# ProPrj_OASman_SMD_update_2025-02-10.net
KiCad netlist of a schematic drawn in EasyEDA Pro
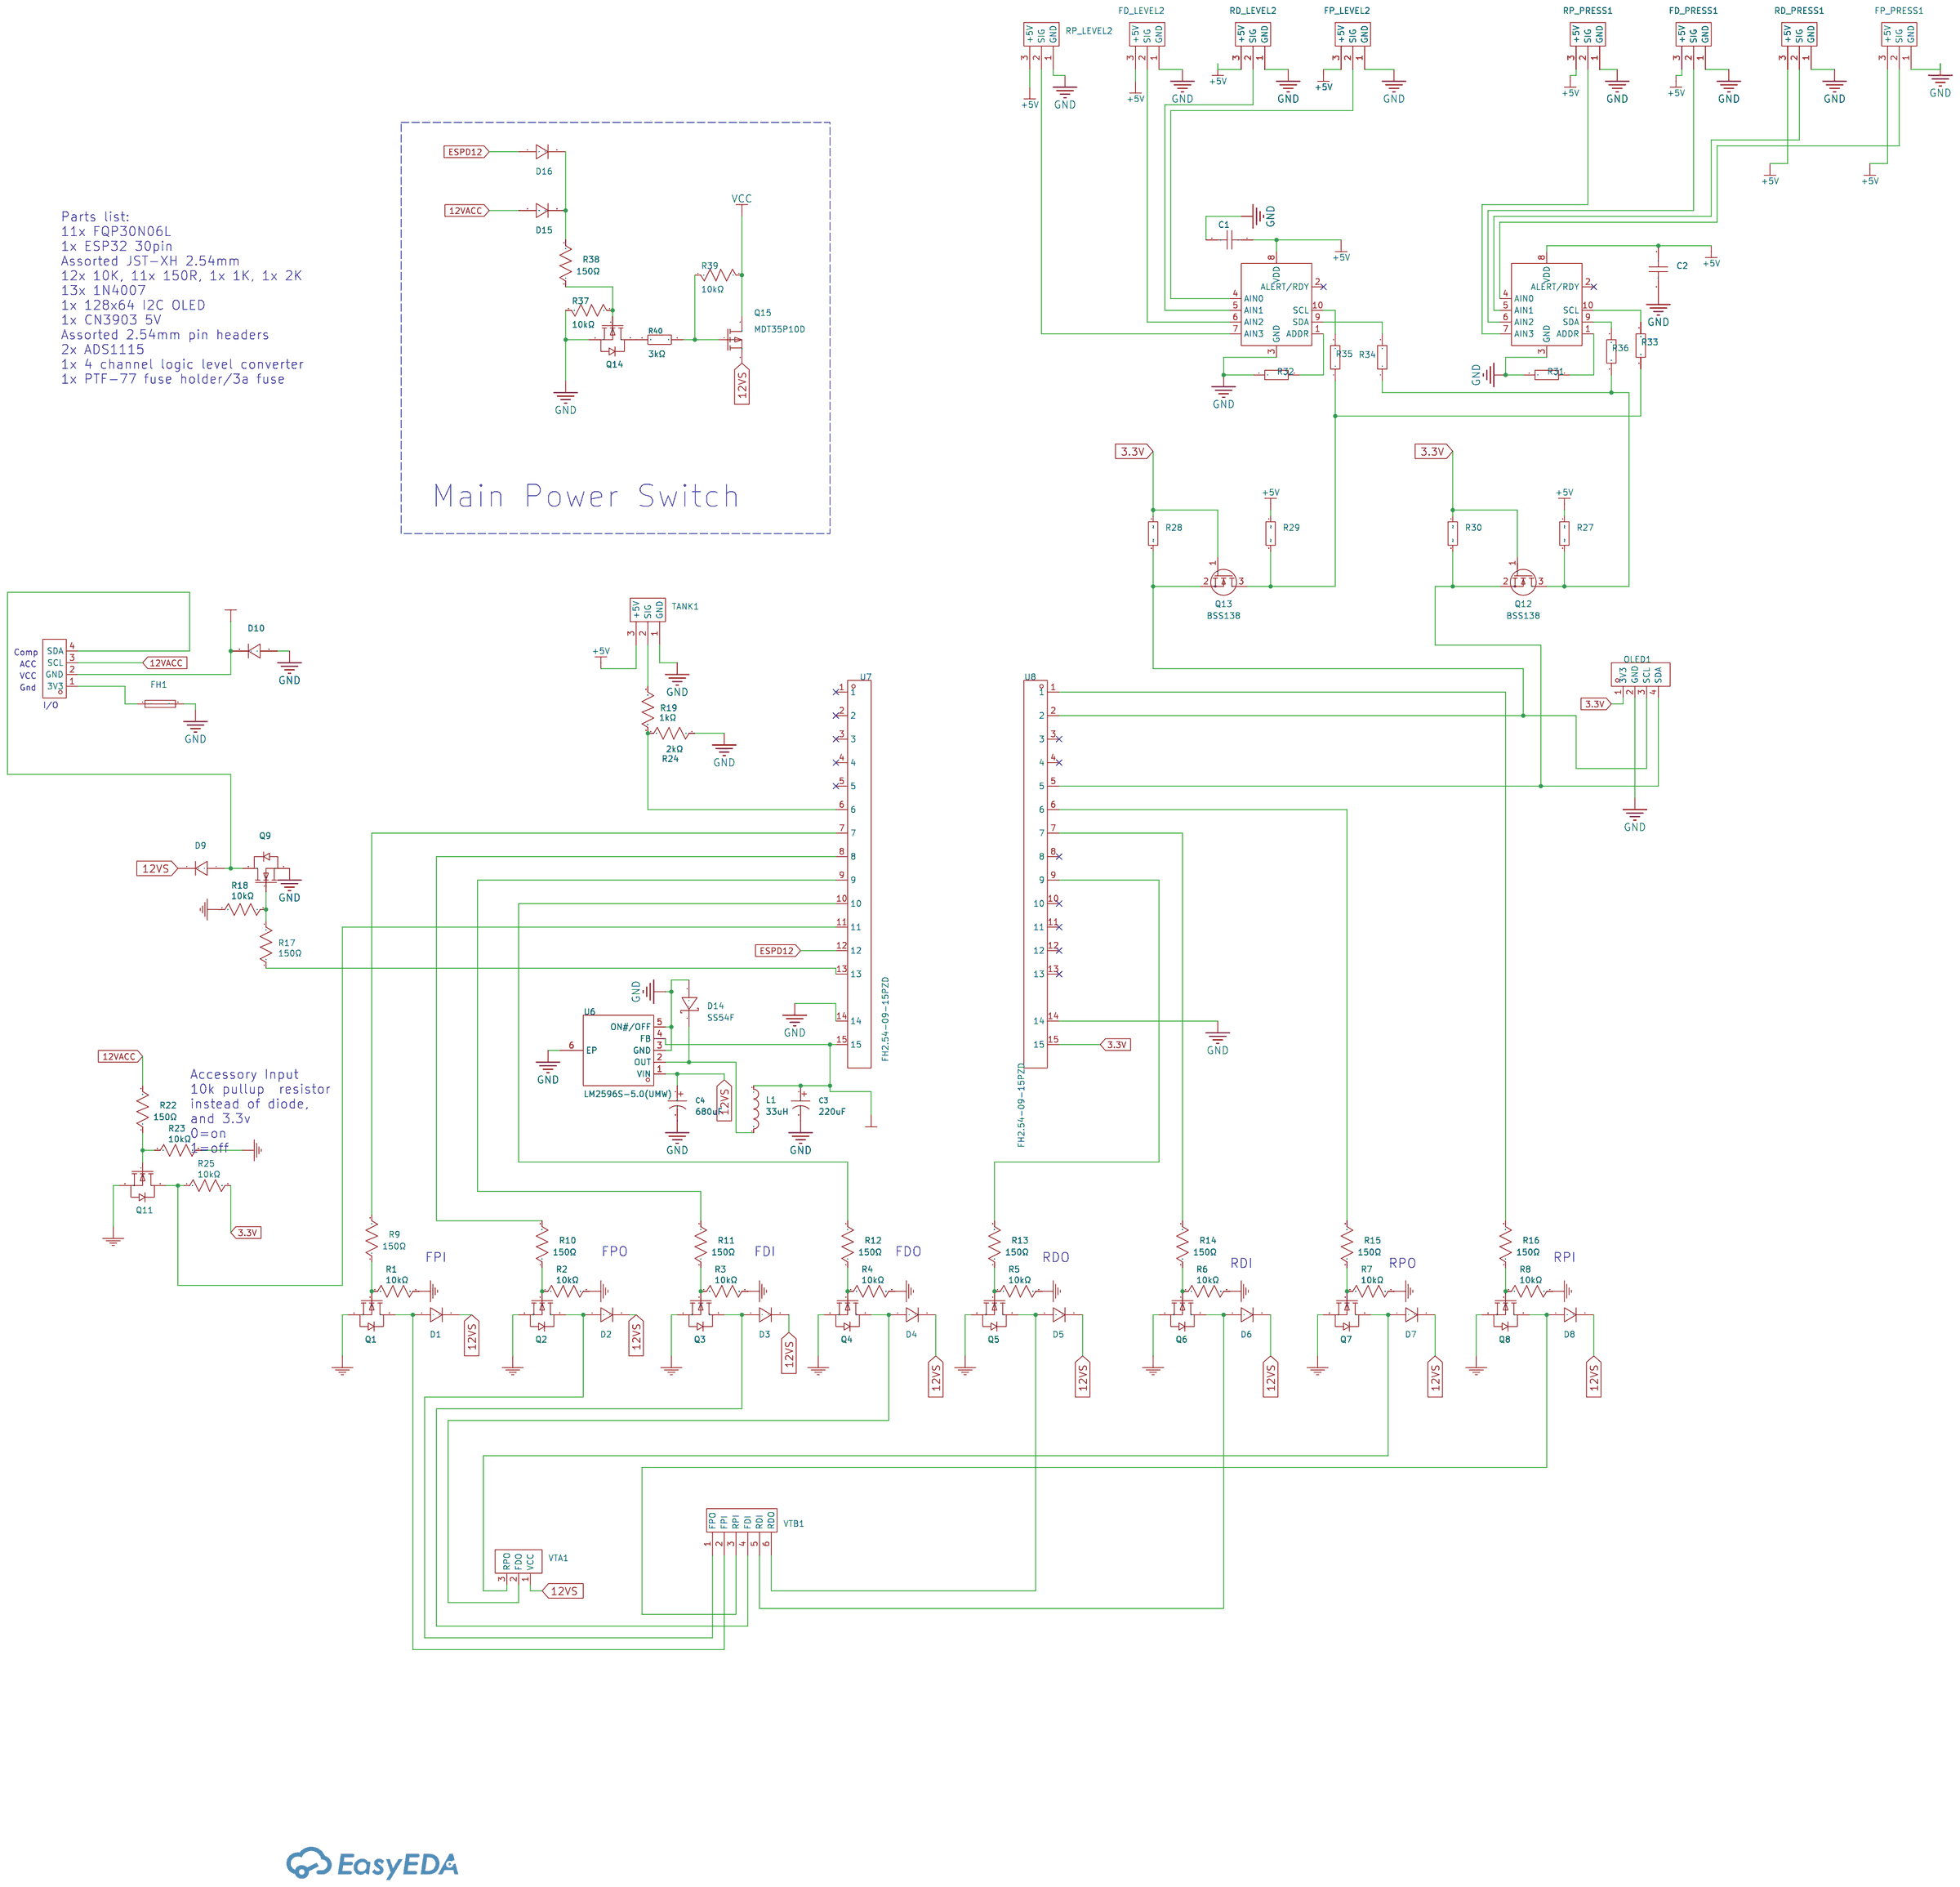
[diagram p0: schematic sheet]

(export (version "E")
  (design (tool "Eeschema 10.0.6"))
  (components
    (comp (ref "C1")
      (value "1uF")
      (footprint "easyedapro:C0603")
      (fields
        (field (name "Manufacturer Part") "GRM188R61H105KAALD")
        (field (name "Manufacturer") "muRata(村田)")
      )
      (libsource (lib "easyedapro") (part "GRM188R61H105KAALD"))
    )
    (comp (ref "C2")
      (value "1uF")
      (footprint "easyedapro:C0603")
      (fields
        (field (name "Manufacturer Part") "GRM188R61H105KAALD")
        (field (name "Manufacturer") "muRata(村田)")
      )
      (libsource (lib "easyedapro") (part "GRM188R61H105KAALD"))
    )
    (comp (ref "C3")
      (value "220uF")
      (footprint "easyedapro:CAP-SMD_BD6.3-L6.6-W6.6-FD")
      (fields (field (name "Manufacturer Part") "CK1C221M-CRE77") (field (name "Manufacturer") "ST(先科)"))
      (libsource (lib "easyedapro") (part "CK1C221M-CRE77"))
    )
    (comp (ref "C4")
      (value "680uF")
      (footprint "easyedapro:CAP-SMD_BD10.0-L10.3-W10.3-LS11.3-FD")
      (fields (field (name "Manufacturer Part") "VT1E681M1013") (field (name "Manufacturer") "HONOR(荣誉)"))
      (libsource (lib "easyedapro") (part "CVT1E681M1013"))
    )
    (comp (ref "CN1")
      (value "XH-4A绿色")
      (footprint "easyedapro:CONN-TH_XH-4A-1")
      (fields (field (name "Manufacturer") "BOOMELE(博穆精密)"))
      (libsource (lib "easyedapro") (part "XH-4A绿色"))
    )
    (comp (ref "D1") (value "1N4007") (libsource (lib "easyedapro") (part "1N4007")))
    (comp (ref "D2") (value "1N4007") (libsource (lib "easyedapro") (part "1N4007")))
    (comp (ref "D3") (value "1N4007") (libsource (lib "easyedapro") (part "1N4007")))
    (comp (ref "D4") (value "1N4007") (libsource (lib "easyedapro") (part "1N4007")))
    (comp (ref "D5") (value "1N4007") (libsource (lib "easyedapro") (part "1N4007")))
    (comp (ref "D6") (value "1N4007") (libsource (lib "easyedapro") (part "1N4007")))
    (comp (ref "D7") (value "1N4007") (libsource (lib "easyedapro") (part "1N4007")))
    (comp (ref "D8") (value "1N4007") (libsource (lib "easyedapro") (part "1N4007")))
    (comp (ref "D9") (value "1N4007") (libsource (lib "easyedapro") (part "1N4007")))
    (comp (ref "D10") (value "1N4007") (libsource (lib "easyedapro") (part "1N4007")))
    (comp (ref "D14")
      (value "SS54F")
      (footprint "easyedapro:SMAF_L3.5-W2.6-LS4.7-FD")
      (fields (field (name "Manufacturer") "High Diode(海德)"))
      (libsource (lib "easyedapro") (part "SS54F_C524830"))
    )
    (comp (ref "D15") (value "1N4007") (libsource (lib "easyedapro") (part "1N4007")))
    (comp (ref "D16") (value "1N4007") (libsource (lib "easyedapro") (part "1N4007")))
    (comp (ref "FD_LEVEL2")
      (value "XH-3A")
      (footprint "easyedapro:CONN-TH_XH-3A")
      (fields (field (name "Manufacturer") "BOOMELE(博穆精密)"))
      (libsource (lib "easyedapro") (part "XH-3A"))
    )
    (comp (ref "FD_PRESS1")
      (value "XH-3A")
      (footprint "easyedapro:CONN-TH_XH-3A")
      (fields (field (name "Manufacturer") "BOOMELE(博穆精密)"))
      (libsource (lib "easyedapro") (part "XH-3A"))
    )
    (comp (ref "FH1")
      (value "PTF-77")
      (description "Fuseholder Type:- Voltage Rating:250V Current Rating:10A Fuse Type:- Fuse Size:-")
      (libsource (lib "easyedapro") (part "PTF-77"))
    )
    (comp (ref "FP_LEVEL2")
      (value "XH-3A")
      (footprint "easyedapro:CONN-TH_XH-3A")
      (fields (field (name "Manufacturer") "BOOMELE(博穆精密)"))
      (libsource (lib "easyedapro") (part "XH-3A"))
    )
    (comp (ref "FP_PRESS1")
      (value "XH-3A")
      (footprint "easyedapro:CONN-TH_XH-3A")
      (fields (field (name "Manufacturer") "BOOMELE(博穆精密)"))
      (libsource (lib "easyedapro") (part "XH-3A"))
    )
    (comp (ref "L1")
      (value "33uH")
      (footprint "easyedapro:IND-SMD_L10.8-W10.0_SLO1040H")
      (fields
        (field (name "Manufacturer Part") "SLO1040H330MTT")
        (field (name "Manufacturer") "Sunltech(韩国顺磁)")
      )
      (libsource (lib "easyedapro") (part "SLO1040H330MTT"))
    )
    (comp (ref "OLED1")
      (value "XH-4A绿色")
      (footprint "easyedapro:CONN-TH_XH-4A-1")
      (fields (field (name "Manufacturer") "BOOMELE(博穆精密)"))
      (libsource (lib "easyedapro") (part "XH-4A绿色"))
    )
    (comp (ref "Q1") (value "MDT30N06L") (libsource (lib "easyedapro") (part "FQP30N06L")))
    (comp (ref "Q2") (value "MDT30N06L") (libsource (lib "easyedapro") (part "FQP30N06L")))
    (comp (ref "Q3") (value "MDT30N06L") (libsource (lib "easyedapro") (part "FQP30N06L")))
    (comp (ref "Q4") (value "MDT30N06L") (libsource (lib "easyedapro") (part "FQP30N06L")))
    (comp (ref "Q5") (value "MDT30N06L") (libsource (lib "easyedapro") (part "FQP30N06L")))
    (comp (ref "Q6") (value "MDT30N06L") (libsource (lib "easyedapro") (part "FQP30N06L")))
    (comp (ref "Q7") (value "MDT30N06L") (libsource (lib "easyedapro") (part "FQP30N06L")))
    (comp (ref "Q8") (value "MDT30N06L") (libsource (lib "easyedapro") (part "FQP30N06L")))
    (comp (ref "Q9") (value "MDT30N06L") (libsource (lib "easyedapro") (part "FQP30N06L")))
    (comp (ref "Q11") (value "MDT30N06L") (libsource (lib "easyedapro") (part "FQP30N06L")))
    (comp (ref "Q12")
      (value "BSS138")
      (footprint "easyedapro:PCM_Package_TO_SOT_SMD_AKL:SOT-23")
      (description "SOT-23 N-MOSFET enchancement mode transistor, 50V, 200mA, 300mW, Alternate KiCAD Library")
      (libsource (lib "easyedapro") (part "PCM_Transistor_MOSFET_AKL_BSS138"))
    )
    (comp (ref "Q13")
      (value "BSS138")
      (footprint "easyedapro:PCM_Package_TO_SOT_SMD_AKL:SOT-23")
      (description "SOT-23 N-MOSFET enchancement mode transistor, 50V, 200mA, 300mW, Alternate KiCAD Library")
      (libsource (lib "easyedapro") (part "PCM_Transistor_MOSFET_AKL_BSS138"))
    )
    (comp (ref "Q14") (value "MDT30N06L") (libsource (lib "easyedapro") (part "FQP30N06L")))
    (comp (ref "Q15")
      (value "MDT35P10D")
      (footprint "easyedapro:TO-252-2_L6.6-W6.1-P4.57-LS9.9-BR-CW")
      (fields (field (name "Manufacturer") "minos(迈诺斯)"))
      (libsource (lib "easyedapro") (part "MDT35P10D"))
    )
    (comp (ref "R1")
      (value "10kΩ")
      (fields (field (name "Manufacturer") "UNI-ROYAL(厚声)"))
      (libsource (lib "easyedapro") (part "10k"))
    )
    (comp (ref "R2")
      (value "10kΩ")
      (fields (field (name "Manufacturer") "UNI-ROYAL(厚声)"))
      (libsource (lib "easyedapro") (part "10k"))
    )
    (comp (ref "R3")
      (value "10kΩ")
      (fields (field (name "Manufacturer") "UNI-ROYAL(厚声)"))
      (libsource (lib "easyedapro") (part "10k"))
    )
    (comp (ref "R4")
      (value "10kΩ")
      (fields (field (name "Manufacturer") "UNI-ROYAL(厚声)"))
      (libsource (lib "easyedapro") (part "10k"))
    )
    (comp (ref "R5")
      (value "10kΩ")
      (fields (field (name "Manufacturer") "UNI-ROYAL(厚声)"))
      (libsource (lib "easyedapro") (part "10k"))
    )
    (comp (ref "R6")
      (value "10kΩ")
      (fields (field (name "Manufacturer") "UNI-ROYAL(厚声)"))
      (libsource (lib "easyedapro") (part "10k"))
    )
    (comp (ref "R7")
      (value "10kΩ")
      (fields (field (name "Manufacturer") "UNI-ROYAL(厚声)"))
      (libsource (lib "easyedapro") (part "10k"))
    )
    (comp (ref "R8")
      (value "10kΩ")
      (fields (field (name "Manufacturer") "UNI-ROYAL(厚声)"))
      (libsource (lib "easyedapro") (part "10k"))
    )
    (comp (ref "R9")
      (value "150Ω")
      (fields (field (name "Manufacturer") "UNI-ROYAL(厚声)"))
      (libsource (lib "easyedapro") (part "150R"))
    )
    (comp (ref "R10")
      (value "150Ω")
      (fields (field (name "Manufacturer") "UNI-ROYAL(厚声)"))
      (libsource (lib "easyedapro") (part "150R"))
    )
    (comp (ref "R11")
      (value "150Ω")
      (fields (field (name "Manufacturer") "UNI-ROYAL(厚声)"))
      (libsource (lib "easyedapro") (part "150R"))
    )
    (comp (ref "R12")
      (value "150Ω")
      (fields (field (name "Manufacturer") "UNI-ROYAL(厚声)"))
      (libsource (lib "easyedapro") (part "150R"))
    )
    (comp (ref "R13")
      (value "150Ω")
      (fields (field (name "Manufacturer") "UNI-ROYAL(厚声)"))
      (libsource (lib "easyedapro") (part "150R"))
    )
    (comp (ref "R14")
      (value "150Ω")
      (fields (field (name "Manufacturer") "UNI-ROYAL(厚声)"))
      (libsource (lib "easyedapro") (part "150R"))
    )
    (comp (ref "R15")
      (value "150Ω")
      (fields (field (name "Manufacturer") "UNI-ROYAL(厚声)"))
      (libsource (lib "easyedapro") (part "150R"))
    )
    (comp (ref "R16")
      (value "150Ω")
      (fields (field (name "Manufacturer") "UNI-ROYAL(厚声)"))
      (libsource (lib "easyedapro") (part "150R"))
    )
    (comp (ref "R17")
      (value "150Ω")
      (fields (field (name "Manufacturer") "UNI-ROYAL(厚声)"))
      (libsource (lib "easyedapro") (part "150R"))
    )
    (comp (ref "R18")
      (value "10kΩ")
      (fields (field (name "Manufacturer") "UNI-ROYAL(厚声)"))
      (libsource (lib "easyedapro") (part "10k"))
    )
    (comp (ref "R19")
      (value "1kΩ")
      (fields (field (name "Manufacturer") "UNI-ROYAL(厚声)"))
      (libsource (lib "easyedapro") (part "1K"))
    )
    (comp (ref "R22")
      (value "150Ω")
      (fields (field (name "Manufacturer") "UNI-ROYAL(厚声)"))
      (libsource (lib "easyedapro") (part "150R"))
    )
    (comp (ref "R23")
      (value "10kΩ")
      (fields (field (name "Manufacturer") "UNI-ROYAL(厚声)"))
      (libsource (lib "easyedapro") (part "10k"))
    )
    (comp (ref "R24")
      (value "2kΩ")
      (fields (field (name "Manufacturer") "UNI-ROYAL(厚声)"))
      (libsource (lib "easyedapro") (part "2K"))
    )
    (comp (ref "R25")
      (value "10kΩ")
      (fields (field (name "Manufacturer") "UNI-ROYAL(厚声)"))
      (libsource (lib "easyedapro") (part "10k"))
    )
    (comp (ref "R27")
      (value "10k_0402")
      (footprint "easyedapro:Resistor_SMD:R_0402_1005Metric")
      (description "10k, 1%, 1/16W, 0603")
      (fields (field (name "Manufacturer") "Yageo"))
      (libsource (lib "easyedapro") (part "PCM_4ms_Resistor_10k_0402"))
    )
    (comp (ref "R28")
      (value "10k_0402")
      (footprint "easyedapro:Resistor_SMD:R_0402_1005Metric")
      (description "10k, 1%, 1/16W, 0603")
      (fields (field (name "Manufacturer") "Yageo"))
      (libsource (lib "easyedapro") (part "PCM_4ms_Resistor_10k_0402"))
    )
    (comp (ref "R29")
      (value "10k_0402")
      (footprint "easyedapro:Resistor_SMD:R_0402_1005Metric")
      (description "10k, 1%, 1/16W, 0603")
      (fields (field (name "Manufacturer") "Yageo"))
      (libsource (lib "easyedapro") (part "PCM_4ms_Resistor_10k_0402"))
    )
    (comp (ref "R30")
      (value "10k_0402")
      (footprint "easyedapro:Resistor_SMD:R_0402_1005Metric")
      (description "10k, 1%, 1/16W, 0603")
      (fields (field (name "Manufacturer") "Yageo"))
      (libsource (lib "easyedapro") (part "PCM_4ms_Resistor_10k_0402"))
    )
    (comp (ref "R31")
      (value "10K")
      (footprint "easyedapro:R0402")
      (libsource (lib "easyedapro") (part "Res"))
    )
    (comp (ref "R32")
      (value "10K")
      (footprint "easyedapro:R0402")
      (libsource (lib "easyedapro") (part "Res"))
    )
    (comp (ref "R33")
      (value "10K")
      (footprint "easyedapro:R0402")
      (libsource (lib "easyedapro") (part "Res"))
    )
    (comp (ref "R34")
      (value "10K")
      (footprint "easyedapro:R0402")
      (libsource (lib "easyedapro") (part "Res"))
    )
    (comp (ref "R35")
      (value "10K")
      (footprint "easyedapro:R0402")
      (libsource (lib "easyedapro") (part "Res"))
    )
    (comp (ref "R36")
      (value "10K")
      (footprint "easyedapro:R0402")
      (libsource (lib "easyedapro") (part "Res"))
    )
    (comp (ref "R37")
      (value "10kΩ")
      (fields (field (name "Manufacturer") "UNI-ROYAL(厚声)"))
      (libsource (lib "easyedapro") (part "10k"))
    )
    (comp (ref "R38")
      (value "150Ω")
      (fields (field (name "Manufacturer") "UNI-ROYAL(厚声)"))
      (libsource (lib "easyedapro") (part "150R"))
    )
    (comp (ref "R39")
      (value "10kΩ")
      (fields (field (name "Manufacturer") "UNI-ROYAL(厚声)"))
      (libsource (lib "easyedapro") (part "10k"))
    )
    (comp (ref "R40")
      (value "3kΩ")
      (footprint "easyedapro:R1206")
      (fields
        (field (name "Manufacturer Part") "1206W4F3001T5E")
        (field (name "Manufacturer") "UNI-ROYAL(厚声)")
      )
      (libsource (lib "easyedapro") (part "1206W4F3001T5E"))
    )
    (comp (ref "RD_LEVEL2")
      (value "XH-3A")
      (footprint "easyedapro:CONN-TH_XH-3A")
      (fields (field (name "Manufacturer") "BOOMELE(博穆精密)"))
      (libsource (lib "easyedapro") (part "XH-3A"))
    )
    (comp (ref "RD_PRESS1")
      (value "XH-3A")
      (footprint "easyedapro:CONN-TH_XH-3A")
      (fields (field (name "Manufacturer") "BOOMELE(博穆精密)"))
      (libsource (lib "easyedapro") (part "XH-3A"))
    )
    (comp (ref "RP_LEVEL2")
      (value "XH-3A")
      (footprint "easyedapro:CONN-TH_XH-3A")
      (fields (field (name "Manufacturer") "BOOMELE(博穆精密)"))
      (libsource (lib "easyedapro") (part "XH-3A"))
    )
    (comp (ref "RP_PRESS1")
      (value "XH-3A")
      (footprint "easyedapro:CONN-TH_XH-3A")
      (fields (field (name "Manufacturer") "BOOMELE(博穆精密)"))
      (libsource (lib "easyedapro") (part "XH-3A"))
    )
    (comp (ref "TANK1")
      (value "XH-3A")
      (footprint "easyedapro:CONN-TH_XH-3A")
      (fields (field (name "Manufacturer") "BOOMELE(博穆精密)"))
      (libsource (lib "easyedapro") (part "XH-3A"))
    )
    (comp (ref "U4")
      (value "ADS1115IDGSR")
      (fields (field (name "Manufacturer") "TI(德州仪器)"))
      (libsource (lib "easyedapro") (part "Analog_ADC_ADS1115IDGS"))
    )
    (comp (ref "U5")
      (value "ADS1115IDGSR")
      (fields (field (name "Manufacturer") "TI(德州仪器)"))
      (libsource (lib "easyedapro") (part "Analog_ADC_ADS1115IDGS"))
    )
    (comp (ref "U6")
      (value "LM2596S-5.0(UMW)")
      (footprint "easyedapro:TO-263-5_L10.2-W8.9-P1.70-BR")
      (fields (field (name "Manufacturer") "UMW(友台半导体)"))
      (libsource (lib "easyedapro") (part "LM2596S-5.0"))
    )
    (comp (ref "U7")
      (value "FH2.54-09-15PZD")
      (footprint "easyedapro:HDR-TH_15P-P2.54-V-F-1")
      (fields (field (name "Manufacturer") "XUNPU(讯普)"))
      (libsource (lib "easyedapro") (part "FH2.54-09-15PZD"))
    )
    (comp (ref "U8")
      (value "FH2.54-09-15PZD")
      (footprint "easyedapro:HDR-TH_15P-P2.54-V-F-1")
      (fields (field (name "Manufacturer") "XUNPU(讯普)"))
      (libsource (lib "easyedapro") (part "FH2.54-09-15PZD"))
    )
    (comp (ref "VTA1") (value "XH-3A") (libsource (lib "easyedapro") (part "Valvetable A")))
    (comp (ref "VTB1")
      (value "XH-6A")
      (footprint "easyedapro:CONN-TH_6P-P2.50_XH-6A")
      (fields (field (name "Manufacturer") "BOOMELE(博穆精密)"))
      (libsource (lib "easyedapro") (part "XH-6A"))
    )
  )
  (nets
    (net (code "1") (name "+5V") (class "Default")
      (node (ref "C1") (pin "1") (pinfunction "1_1") (pintype "unspecified"))
      (node (ref "C2") (pin "1") (pinfunction "1_1") (pintype "unspecified"))
      (node (ref "C3") (pin "1") (pinfunction "1_1") (pintype "input"))
      (node (ref "FD_LEVEL2") (pin "3") (pinfunction "+5V_3") (pintype "input"))
      (node (ref "FD_PRESS1") (pin "3") (pinfunction "+5V_3") (pintype "input"))
      (node (ref "FP_LEVEL2") (pin "3") (pinfunction "+5V_3") (pintype "input"))
      (node (ref "FP_PRESS1") (pin "3") (pinfunction "+5V_3") (pintype "input"))
      (node (ref "L1") (pin "1") (pinfunction "1_1") (pintype "unspecified"))
      (node (ref "R27") (pin "1") (pinfunction "~_1") (pintype "unspecified"))
      (node (ref "R29") (pin "1") (pinfunction "~_1") (pintype "unspecified"))
      (node (ref "RD_LEVEL2") (pin "3") (pinfunction "+5V_3") (pintype "input"))
      (node (ref "RD_PRESS1") (pin "3") (pinfunction "+5V_3") (pintype "input"))
      (node (ref "RP_LEVEL2") (pin "3") (pinfunction "+5V_3") (pintype "input"))
      (node (ref "RP_PRESS1") (pin "3") (pinfunction "+5V_3") (pintype "input"))
      (node (ref "TANK1") (pin "3") (pinfunction "+5V_3") (pintype "input"))
      (node (ref "U4") (pin "8") (pinfunction "VDD_8") (pintype "unspecified"))
      (node (ref "U5") (pin "8") (pinfunction "VDD_8") (pintype "unspecified"))
      (node (ref "U6") (pin "4") (pinfunction "FB_4") (pintype "unspecified"))
      (node (ref "U7") (pin "15") (pinfunction "15_15") (pintype "unspecified"))
    )
    (net (code "2") (name "3.3V") (class "Default")
      (node (ref "OLED1") (pin "1") (pinfunction "3V3_1") (pintype "input"))
      (node (ref "Q12") (pin "1") (pinfunction "G_1") (pintype "input"))
      (node (ref "Q13") (pin "1") (pinfunction "G_1") (pintype "input"))
      (node (ref "R25") (pin "2") (pinfunction "2_2") (pintype "unspecified"))
      (node (ref "R28") (pin "1") (pinfunction "~_1") (pintype "unspecified"))
      (node (ref "R30") (pin "1") (pinfunction "~_1") (pintype "unspecified"))
      (node (ref "U8") (pin "15") (pinfunction "15_15") (pintype "unspecified"))
    )
    (net (code "3") (name "12VACC") (class "Default")
      (node (ref "CN1") (pin "3") (pinfunction "SCL_3") (pintype "input"))
      (node (ref "D15") (pin "1") (pinfunction "A_1") (pintype "unspecified"))
      (node (ref "R22") (pin "2") (pinfunction "2_2") (pintype "unspecified"))
    )
    (net (code "4") (name "12VS") (class "Default")
      (node (ref "C4") (pin "1") (pinfunction "1_1") (pintype "input"))
      (node (ref "D1") (pin "2") (pinfunction "K_2") (pintype "unspecified"))
      (node (ref "D2") (pin "2") (pinfunction "K_2") (pintype "unspecified"))
      (node (ref "D3") (pin "2") (pinfunction "K_2") (pintype "unspecified"))
      (node (ref "D4") (pin "2") (pinfunction "K_2") (pintype "unspecified"))
      (node (ref "D5") (pin "2") (pinfunction "K_2") (pintype "unspecified"))
      (node (ref "D6") (pin "2") (pinfunction "K_2") (pintype "unspecified"))
      (node (ref "D7") (pin "2") (pinfunction "K_2") (pintype "unspecified"))
      (node (ref "D8") (pin "2") (pinfunction "K_2") (pintype "unspecified"))
      (node (ref "D9") (pin "2") (pinfunction "K_2") (pintype "unspecified"))
      (node (ref "Q15") (pin "3") (pinfunction "S_3") (pintype "unspecified"))
      (node (ref "U6") (pin "1") (pinfunction "VIN_1") (pintype "unspecified"))
      (node (ref "VTA1") (pin "1") (pinfunction "VCC_1") (pintype "unspecified"))
    )
    (net (code "5") (name "ESPD12") (class "Default")
      (node (ref "D16") (pin "1") (pinfunction "A_1") (pintype "unspecified"))
      (node (ref "U7") (pin "12") (pinfunction "12_12") (pintype "unspecified"))
    )
    (net (code "6") (name "GND") (class "Default")
      (node (ref "C1") (pin "2") (pinfunction "2_2") (pintype "unspecified"))
      (node (ref "C2") (pin "2") (pinfunction "2_2") (pintype "unspecified"))
      (node (ref "C3") (pin "2") (pinfunction "2_2") (pintype "input"))
      (node (ref "C4") (pin "2") (pinfunction "2_2") (pintype "input"))
      (node (ref "D10") (pin "1") (pinfunction "A_1") (pintype "unspecified"))
      (node (ref "D14") (pin "1") (pinfunction "A_1") (pintype "input"))
      (node (ref "FD_LEVEL2") (pin "1") (pinfunction "GND_1") (pintype "input"))
      (node (ref "FD_PRESS1") (pin "1") (pinfunction "GND_1") (pintype "input"))
      (node (ref "FH1") (pin "2") (pinfunction "2_2") (pintype "unspecified"))
      (node (ref "FP_LEVEL2") (pin "1") (pinfunction "GND_1") (pintype "input"))
      (node (ref "FP_PRESS1") (pin "1") (pinfunction "GND_1") (pintype "input"))
      (node (ref "OLED1") (pin "2") (pinfunction "GND_2") (pintype "input"))
      (node (ref "Q1") (pin "3") (pinfunction "S_3") (pintype "unspecified"))
      (node (ref "Q11") (pin "3") (pinfunction "S_3") (pintype "unspecified"))
      (node (ref "Q14") (pin "3") (pinfunction "S_3") (pintype "unspecified"))
      (node (ref "Q2") (pin "3") (pinfunction "S_3") (pintype "unspecified"))
      (node (ref "Q3") (pin "3") (pinfunction "S_3") (pintype "unspecified"))
      (node (ref "Q4") (pin "3") (pinfunction "S_3") (pintype "unspecified"))
      (node (ref "Q5") (pin "3") (pinfunction "S_3") (pintype "unspecified"))
      (node (ref "Q6") (pin "3") (pinfunction "S_3") (pintype "unspecified"))
      (node (ref "Q7") (pin "3") (pinfunction "S_3") (pintype "unspecified"))
      (node (ref "Q8") (pin "3") (pinfunction "S_3") (pintype "unspecified"))
      (node (ref "Q9") (pin "3") (pinfunction "S_3") (pintype "unspecified"))
      (node (ref "R1") (pin "2") (pinfunction "2_2") (pintype "unspecified"))
      (node (ref "R18") (pin "2") (pinfunction "2_2") (pintype "unspecified"))
      (node (ref "R2") (pin "2") (pinfunction "2_2") (pintype "unspecified"))
      (node (ref "R23") (pin "2") (pinfunction "2_2") (pintype "unspecified"))
      (node (ref "R24") (pin "1") (pinfunction "1_1") (pintype "unspecified"))
      (node (ref "R3") (pin "2") (pinfunction "2_2") (pintype "unspecified"))
      (node (ref "R31") (pin "1") (pinfunction "1_1") (pintype "input"))
      (node (ref "R32") (pin "1") (pinfunction "1_1") (pintype "input"))
      (node (ref "R37") (pin "2") (pinfunction "2_2") (pintype "unspecified"))
      (node (ref "R4") (pin "2") (pinfunction "2_2") (pintype "unspecified"))
      (node (ref "R5") (pin "2") (pinfunction "2_2") (pintype "unspecified"))
      (node (ref "R6") (pin "2") (pinfunction "2_2") (pintype "unspecified"))
      (node (ref "R7") (pin "2") (pinfunction "2_2") (pintype "unspecified"))
      (node (ref "R8") (pin "2") (pinfunction "2_2") (pintype "unspecified"))
      (node (ref "RD_LEVEL2") (pin "1") (pinfunction "GND_1") (pintype "input"))
      (node (ref "RD_PRESS1") (pin "1") (pinfunction "GND_1") (pintype "input"))
      (node (ref "RP_LEVEL2") (pin "1") (pinfunction "GND_1") (pintype "input"))
      (node (ref "RP_PRESS1") (pin "1") (pinfunction "GND_1") (pintype "input"))
      (node (ref "TANK1") (pin "1") (pinfunction "GND_1") (pintype "input"))
      (node (ref "U4") (pin "3") (pinfunction "GND_3") (pintype "unspecified"))
      (node (ref "U5") (pin "3") (pinfunction "GND_3") (pintype "unspecified"))
      (node (ref "U6") (pin "3") (pinfunction "GND_3") (pintype "unspecified"))
      (node (ref "U6") (pin "5") (pinfunction "ON#/OFF_5") (pintype "unspecified"))
      (node (ref "U6") (pin "6") (pinfunction "EP_6") (pintype "unspecified"))
      (node (ref "U7") (pin "14") (pinfunction "14_14") (pintype "unspecified"))
      (node (ref "U8") (pin "14") (pinfunction "14_14") (pintype "unspecified"))
    )
    (net (code "7") (name "Net-(CN1-3V3)") (class "Default")
      (node (ref "CN1") (pin "1") (pinfunction "3V3_1") (pintype "input"))
      (node (ref "FH1") (pin "1") (pinfunction "1_1") (pintype "unspecified"))
    )
    (net (code "8") (name "Net-(CN1-SDA)") (class "Default")
      (node (ref "CN1") (pin "4") (pinfunction "SDA_4") (pintype "input"))
      (node (ref "D9") (pin "1") (pinfunction "A_1") (pintype "unspecified"))
      (node (ref "Q9") (pin "2") (pinfunction "D_2") (pintype "unspecified"))
    )
    (net (code "9") (name "Net-(D1-A)") (class "Default")
      (node (ref "D1") (pin "1") (pinfunction "A_1") (pintype "unspecified"))
      (node (ref "Q1") (pin "2") (pinfunction "D_2") (pintype "unspecified"))
      (node (ref "VTB1") (pin "2") (pinfunction "FPI_2") (pintype "input"))
    )
    (net (code "10") (name "Net-(D2-A)") (class "Default")
      (node (ref "D2") (pin "1") (pinfunction "A_1") (pintype "unspecified"))
      (node (ref "Q2") (pin "2") (pinfunction "D_2") (pintype "unspecified"))
      (node (ref "VTB1") (pin "1") (pinfunction "FPO_1") (pintype "input"))
    )
    (net (code "11") (name "Net-(D3-A)") (class "Default")
      (node (ref "D3") (pin "1") (pinfunction "A_1") (pintype "unspecified"))
      (node (ref "Q3") (pin "2") (pinfunction "D_2") (pintype "unspecified"))
      (node (ref "VTB1") (pin "4") (pinfunction "FDI_4") (pintype "input"))
    )
    (net (code "12") (name "Net-(D4-A)") (class "Default")
      (node (ref "D4") (pin "1") (pinfunction "A_1") (pintype "unspecified"))
      (node (ref "Q4") (pin "2") (pinfunction "D_2") (pintype "unspecified"))
      (node (ref "VTA1") (pin "2") (pinfunction "FDO_2") (pintype "unspecified"))
    )
    (net (code "13") (name "Net-(D5-A)") (class "Default")
      (node (ref "D5") (pin "1") (pinfunction "A_1") (pintype "unspecified"))
      (node (ref "Q5") (pin "2") (pinfunction "D_2") (pintype "unspecified"))
      (node (ref "VTB1") (pin "6") (pinfunction "RDO_6") (pintype "input"))
    )
    (net (code "14") (name "Net-(D6-A)") (class "Default")
      (node (ref "D6") (pin "1") (pinfunction "A_1") (pintype "unspecified"))
      (node (ref "Q6") (pin "2") (pinfunction "D_2") (pintype "unspecified"))
      (node (ref "VTB1") (pin "5") (pinfunction "RDI_5") (pintype "input"))
    )
    (net (code "15") (name "Net-(D7-A)") (class "Default")
      (node (ref "D7") (pin "1") (pinfunction "A_1") (pintype "unspecified"))
      (node (ref "Q7") (pin "2") (pinfunction "D_2") (pintype "unspecified"))
      (node (ref "VTA1") (pin "3") (pinfunction "RPO_3") (pintype "unspecified"))
    )
    (net (code "16") (name "Net-(D8-A)") (class "Default")
      (node (ref "D8") (pin "1") (pinfunction "A_1") (pintype "unspecified"))
      (node (ref "Q8") (pin "2") (pinfunction "D_2") (pintype "unspecified"))
      (node (ref "VTB1") (pin "3") (pinfunction "RPI_3") (pintype "input"))
    )
    (net (code "17") (name "Net-(D14-K)") (class "Default")
      (node (ref "D14") (pin "2") (pinfunction "K_2") (pintype "input"))
      (node (ref "L1") (pin "2") (pinfunction "2_2") (pintype "unspecified"))
      (node (ref "U6") (pin "2") (pinfunction "OUT_2") (pintype "unspecified"))
    )
    (net (code "18") (name "Net-(D15-K)") (class "Default")
      (node (ref "D15") (pin "2") (pinfunction "K_2") (pintype "unspecified"))
      (node (ref "D16") (pin "2") (pinfunction "K_2") (pintype "unspecified"))
      (node (ref "R38") (pin "2") (pinfunction "2_2") (pintype "unspecified"))
    )
    (net (code "19") (name "Net-(FD_LEVEL2-SIG)") (class "Default")
      (node (ref "FD_LEVEL2") (pin "2") (pinfunction "SIG_2") (pintype "input"))
      (node (ref "U4") (pin "6") (pinfunction "AIN2_6") (pintype "input"))
    )
    (net (code "20") (name "Net-(FD_PRESS1-SIG)") (class "Default")
      (node (ref "FD_PRESS1") (pin "2") (pinfunction "SIG_2") (pintype "input"))
      (node (ref "U5") (pin "6") (pinfunction "AIN2_6") (pintype "input"))
    )
    (net (code "21") (name "Net-(FP_LEVEL2-SIG)") (class "Default")
      (node (ref "FP_LEVEL2") (pin "2") (pinfunction "SIG_2") (pintype "input"))
      (node (ref "U4") (pin "4") (pinfunction "AIN0_4") (pintype "input"))
    )
    (net (code "22") (name "Net-(FP_PRESS1-SIG)") (class "Default")
      (node (ref "FP_PRESS1") (pin "2") (pinfunction "SIG_2") (pintype "input"))
      (node (ref "U5") (pin "4") (pinfunction "AIN0_4") (pintype "input"))
    )
    (net (code "23") (name "Net-(OLED1-SCL)") (class "Default")
      (node (ref "OLED1") (pin "3") (pinfunction "SCL_3") (pintype "input"))
      (node (ref "Q13") (pin "2") (pinfunction "S_2") (pintype "unspecified"))
      (node (ref "R28") (pin "2") (pinfunction "~_2") (pintype "unspecified"))
      (node (ref "U8") (pin "2") (pinfunction "2_2") (pintype "unspecified"))
    )
    (net (code "24") (name "Net-(OLED1-SDA)") (class "Default")
      (node (ref "OLED1") (pin "4") (pinfunction "SDA_4") (pintype "input"))
      (node (ref "Q12") (pin "2") (pinfunction "S_2") (pintype "unspecified"))
      (node (ref "R30") (pin "2") (pinfunction "~_2") (pintype "unspecified"))
      (node (ref "U8") (pin "5") (pinfunction "5_5") (pintype "unspecified"))
    )
    (net (code "25") (name "Net-(Q1-G)") (class "Default")
      (node (ref "Q1") (pin "1") (pinfunction "G_1") (pintype "unspecified"))
      (node (ref "R1") (pin "1") (pinfunction "1_1") (pintype "unspecified"))
      (node (ref "R9") (pin "1") (pinfunction "1_1") (pintype "unspecified"))
    )
    (net (code "26") (name "Net-(Q2-G)") (class "Default")
      (node (ref "Q2") (pin "1") (pinfunction "G_1") (pintype "unspecified"))
      (node (ref "R10") (pin "1") (pinfunction "1_1") (pintype "unspecified"))
      (node (ref "R2") (pin "1") (pinfunction "1_1") (pintype "unspecified"))
    )
    (net (code "27") (name "Net-(Q3-G)") (class "Default")
      (node (ref "Q3") (pin "1") (pinfunction "G_1") (pintype "unspecified"))
      (node (ref "R11") (pin "1") (pinfunction "1_1") (pintype "unspecified"))
      (node (ref "R3") (pin "1") (pinfunction "1_1") (pintype "unspecified"))
    )
    (net (code "28") (name "Net-(Q4-G)") (class "Default")
      (node (ref "Q4") (pin "1") (pinfunction "G_1") (pintype "unspecified"))
      (node (ref "R12") (pin "1") (pinfunction "1_1") (pintype "unspecified"))
      (node (ref "R4") (pin "1") (pinfunction "1_1") (pintype "unspecified"))
    )
    (net (code "29") (name "Net-(Q5-G)") (class "Default")
      (node (ref "Q5") (pin "1") (pinfunction "G_1") (pintype "unspecified"))
      (node (ref "R13") (pin "1") (pinfunction "1_1") (pintype "unspecified"))
      (node (ref "R5") (pin "1") (pinfunction "1_1") (pintype "unspecified"))
    )
    (net (code "30") (name "Net-(Q6-G)") (class "Default")
      (node (ref "Q6") (pin "1") (pinfunction "G_1") (pintype "unspecified"))
      (node (ref "R14") (pin "1") (pinfunction "1_1") (pintype "unspecified"))
      (node (ref "R6") (pin "1") (pinfunction "1_1") (pintype "unspecified"))
    )
    (net (code "31") (name "Net-(Q7-G)") (class "Default")
      (node (ref "Q7") (pin "1") (pinfunction "G_1") (pintype "unspecified"))
      (node (ref "R15") (pin "1") (pinfunction "1_1") (pintype "unspecified"))
      (node (ref "R7") (pin "1") (pinfunction "1_1") (pintype "unspecified"))
    )
    (net (code "32") (name "Net-(Q8-G)") (class "Default")
      (node (ref "Q8") (pin "1") (pinfunction "G_1") (pintype "unspecified"))
      (node (ref "R16") (pin "1") (pinfunction "1_1") (pintype "unspecified"))
      (node (ref "R8") (pin "1") (pinfunction "1_1") (pintype "unspecified"))
    )
    (net (code "33") (name "Net-(Q9-G)") (class "Default")
      (node (ref "Q9") (pin "1") (pinfunction "G_1") (pintype "unspecified"))
      (node (ref "R17") (pin "1") (pinfunction "1_1") (pintype "unspecified"))
      (node (ref "R18") (pin "1") (pinfunction "1_1") (pintype "unspecified"))
    )
    (net (code "34") (name "Net-(Q11-D)") (class "Default")
      (node (ref "Q11") (pin "2") (pinfunction "D_2") (pintype "unspecified"))
      (node (ref "R25") (pin "1") (pinfunction "1_1") (pintype "unspecified"))
      (node (ref "U7") (pin "11") (pinfunction "11_11") (pintype "unspecified"))
    )
    (net (code "35") (name "Net-(Q11-G)") (class "Default")
      (node (ref "Q11") (pin "1") (pinfunction "G_1") (pintype "unspecified"))
      (node (ref "R22") (pin "1") (pinfunction "1_1") (pintype "unspecified"))
      (node (ref "R23") (pin "1") (pinfunction "1_1") (pintype "unspecified"))
    )
    (net (code "36") (name "Net-(Q12-D)") (class "Default")
      (node (ref "Q12") (pin "3") (pinfunction "D_3") (pintype "unspecified"))
      (node (ref "R27") (pin "2") (pinfunction "~_2") (pintype "unspecified"))
      (node (ref "R34") (pin "1") (pinfunction "1_1") (pintype "input"))
      (node (ref "R36") (pin "1") (pinfunction "1_1") (pintype "input"))
    )
    (net (code "37") (name "Net-(Q13-D)") (class "Default")
      (node (ref "Q13") (pin "3") (pinfunction "D_3") (pintype "unspecified"))
      (node (ref "R29") (pin "2") (pinfunction "~_2") (pintype "unspecified"))
      (node (ref "R33") (pin "1") (pinfunction "1_1") (pintype "input"))
      (node (ref "R35") (pin "1") (pinfunction "1_1") (pintype "input"))
    )
    (net (code "38") (name "Net-(Q14-D)") (class "Default")
      (node (ref "Q14") (pin "2") (pinfunction "D_2") (pintype "unspecified"))
      (node (ref "R40") (pin "1") (pinfunction "1_1") (pintype "input"))
    )
    (net (code "39") (name "Net-(Q14-G)") (class "Default")
      (node (ref "Q14") (pin "1") (pinfunction "G_1") (pintype "unspecified"))
      (node (ref "R37") (pin "1") (pinfunction "1_1") (pintype "unspecified"))
      (node (ref "R38") (pin "1") (pinfunction "1_1") (pintype "unspecified"))
    )
    (net (code "40") (name "Net-(Q15-G)") (class "Default")
      (node (ref "Q15") (pin "1") (pinfunction "G_1") (pintype "unspecified"))
      (node (ref "R39") (pin "2") (pinfunction "2_2") (pintype "unspecified"))
      (node (ref "R40") (pin "2") (pinfunction "2_2") (pintype "input"))
    )
    (net (code "41") (name "Net-(R9-Pad2)") (class "Default")
      (node (ref "R9") (pin "2") (pinfunction "2_2") (pintype "unspecified"))
      (node (ref "U7") (pin "7") (pinfunction "7_7") (pintype "unspecified"))
    )
    (net (code "42") (name "Net-(R10-Pad2)") (class "Default")
      (node (ref "R10") (pin "2") (pinfunction "2_2") (pintype "unspecified"))
      (node (ref "U7") (pin "8") (pinfunction "8_8") (pintype "unspecified"))
    )
    (net (code "43") (name "Net-(R11-Pad2)") (class "Default")
      (node (ref "R11") (pin "2") (pinfunction "2_2") (pintype "unspecified"))
      (node (ref "U7") (pin "9") (pinfunction "9_9") (pintype "unspecified"))
    )
    (net (code "44") (name "Net-(R12-Pad2)") (class "Default")
      (node (ref "R12") (pin "2") (pinfunction "2_2") (pintype "unspecified"))
      (node (ref "U7") (pin "10") (pinfunction "10_10") (pintype "unspecified"))
    )
    (net (code "45") (name "Net-(R13-Pad2)") (class "Default")
      (node (ref "R13") (pin "2") (pinfunction "2_2") (pintype "unspecified"))
      (node (ref "U8") (pin "9") (pinfunction "9_9") (pintype "unspecified"))
    )
    (net (code "46") (name "Net-(R14-Pad2)") (class "Default")
      (node (ref "R14") (pin "2") (pinfunction "2_2") (pintype "unspecified"))
      (node (ref "U8") (pin "7") (pinfunction "7_7") (pintype "unspecified"))
    )
    (net (code "47") (name "Net-(R15-Pad2)") (class "Default")
      (node (ref "R15") (pin "2") (pinfunction "2_2") (pintype "unspecified"))
      (node (ref "U8") (pin "6") (pinfunction "6_6") (pintype "unspecified"))
    )
    (net (code "48") (name "Net-(R16-Pad2)") (class "Default")
      (node (ref "R16") (pin "2") (pinfunction "2_2") (pintype "unspecified"))
      (node (ref "U8") (pin "1") (pinfunction "1_1") (pintype "unspecified"))
    )
    (net (code "49") (name "Net-(R17-Pad2)") (class "Default")
      (node (ref "R17") (pin "2") (pinfunction "2_2") (pintype "unspecified"))
      (node (ref "U7") (pin "13") (pinfunction "13_13") (pintype "unspecified"))
    )
    (net (code "50") (name "Net-(R19-Pad1)") (class "Default")
      (node (ref "R19") (pin "1") (pinfunction "1_1") (pintype "unspecified"))
      (node (ref "R24") (pin "2") (pinfunction "2_2") (pintype "unspecified"))
      (node (ref "U7") (pin "6") (pinfunction "6_6") (pintype "unspecified"))
    )
    (net (code "51") (name "Net-(RD_LEVEL2-SIG)") (class "Default")
      (node (ref "RD_LEVEL2") (pin "2") (pinfunction "SIG_2") (pintype "input"))
      (node (ref "U4") (pin "5") (pinfunction "AIN1_5") (pintype "input"))
    )
    (net (code "52") (name "Net-(RD_PRESS1-SIG)") (class "Default")
      (node (ref "RD_PRESS1") (pin "2") (pinfunction "SIG_2") (pintype "input"))
      (node (ref "U5") (pin "5") (pinfunction "AIN1_5") (pintype "input"))
    )
    (net (code "53") (name "Net-(RP_LEVEL2-SIG)") (class "Default")
      (node (ref "RP_LEVEL2") (pin "2") (pinfunction "SIG_2") (pintype "input"))
      (node (ref "U4") (pin "7") (pinfunction "AIN3_7") (pintype "input"))
    )
    (net (code "54") (name "Net-(RP_PRESS1-SIG)") (class "Default")
      (node (ref "RP_PRESS1") (pin "2") (pinfunction "SIG_2") (pintype "input"))
      (node (ref "U5") (pin "7") (pinfunction "AIN3_7") (pintype "input"))
    )
    (net (code "55") (name "Net-(TANK1-SIG)") (class "Default")
      (node (ref "R19") (pin "2") (pinfunction "2_2") (pintype "unspecified"))
      (node (ref "TANK1") (pin "2") (pinfunction "SIG_2") (pintype "input"))
    )
    (net (code "56") (name "Net-(U4-ADDR)") (class "Default")
      (node (ref "R32") (pin "2") (pinfunction "2_2") (pintype "input"))
      (node (ref "U4") (pin "1") (pinfunction "ADDR_1") (pintype "input"))
    )
    (net (code "57") (name "Net-(U4-SCL)") (class "Default")
      (node (ref "R35") (pin "2") (pinfunction "2_2") (pintype "input"))
      (node (ref "U4") (pin "10") (pinfunction "SCL_10") (pintype "input"))
    )
    (net (code "58") (name "Net-(U4-SDA)") (class "Default")
      (node (ref "R34") (pin "2") (pinfunction "2_2") (pintype "input"))
      (node (ref "U4") (pin "9") (pinfunction "SDA_9") (pintype "bidirectional"))
    )
    (net (code "59") (name "Net-(U5-ADDR)") (class "Default")
      (node (ref "R31") (pin "2") (pinfunction "2_2") (pintype "input"))
      (node (ref "U5") (pin "1") (pinfunction "ADDR_1") (pintype "input"))
    )
    (net (code "60") (name "Net-(U5-SCL)") (class "Default")
      (node (ref "R33") (pin "2") (pinfunction "2_2") (pintype "input"))
      (node (ref "U5") (pin "10") (pinfunction "SCL_10") (pintype "input"))
    )
    (net (code "61") (name "Net-(U5-SDA)") (class "Default")
      (node (ref "R36") (pin "2") (pinfunction "2_2") (pintype "input"))
      (node (ref "U5") (pin "9") (pinfunction "SDA_9") (pintype "bidirectional"))
    )
    (net (code "62") (name "VCC") (class "Default")
      (node (ref "CN1") (pin "2") (pinfunction "GND_2") (pintype "input"))
      (node (ref "D10") (pin "2") (pinfunction "K_2") (pintype "unspecified"))
      (node (ref "Q15") (pin "2") (pinfunction "D_2") (pintype "unspecified"))
      (node (ref "R39") (pin "1") (pinfunction "1_1") (pintype "unspecified"))
    )
    (net (code "63") (name "unconnected-(U4-ALERT{slash}RDY-Pad2)") (class "Default")
      (node (ref "U4") (pin "2") (pinfunction "ALERT/RDY_2") (pintype "output+no_connect"))
    )
    (net (code "64") (name "unconnected-(U5-ALERT{slash}RDY-Pad2)") (class "Default")
      (node (ref "U5") (pin "2") (pinfunction "ALERT/RDY_2") (pintype "output+no_connect"))
    )
    (net (code "65") (name "unconnected-(U7-Pad1)") (class "Default")
      (node (ref "U7") (pin "1") (pinfunction "1_1") (pintype "unspecified+no_connect"))
    )
    (net (code "66") (name "unconnected-(U7-Pad2)") (class "Default")
      (node (ref "U7") (pin "2") (pinfunction "2_2") (pintype "unspecified+no_connect"))
    )
    (net (code "67") (name "unconnected-(U7-Pad3)") (class "Default")
      (node (ref "U7") (pin "3") (pinfunction "3_3") (pintype "unspecified+no_connect"))
    )
    (net (code "68") (name "unconnected-(U7-Pad4)") (class "Default")
      (node (ref "U7") (pin "4") (pinfunction "4_4") (pintype "unspecified+no_connect"))
    )
    (net (code "69") (name "unconnected-(U7-Pad5)") (class "Default")
      (node (ref "U7") (pin "5") (pinfunction "5_5") (pintype "unspecified+no_connect"))
    )
    (net (code "70") (name "unconnected-(U8-Pad3)") (class "Default")
      (node (ref "U8") (pin "3") (pinfunction "3_3") (pintype "unspecified+no_connect"))
    )
    (net (code "71") (name "unconnected-(U8-Pad4)") (class "Default")
      (node (ref "U8") (pin "4") (pinfunction "4_4") (pintype "unspecified+no_connect"))
    )
    (net (code "72") (name "unconnected-(U8-Pad8)") (class "Default")
      (node (ref "U8") (pin "8") (pinfunction "8_8") (pintype "unspecified+no_connect"))
    )
    (net (code "73") (name "unconnected-(U8-Pad10)") (class "Default")
      (node (ref "U8") (pin "10") (pinfunction "10_10") (pintype "unspecified+no_connect"))
    )
    (net (code "74") (name "unconnected-(U8-Pad11)") (class "Default")
      (node (ref "U8") (pin "11") (pinfunction "11_11") (pintype "unspecified+no_connect"))
    )
    (net (code "75") (name "unconnected-(U8-Pad12)") (class "Default")
      (node (ref "U8") (pin "12") (pinfunction "12_12") (pintype "unspecified+no_connect"))
    )
    (net (code "76") (name "unconnected-(U8-Pad13)") (class "Default")
      (node (ref "U8") (pin "13") (pinfunction "13_13") (pintype "unspecified+no_connect"))
    )
  )
)
